# Connectors.net
KiCad netlist of a schematic drawn in Altium Designer
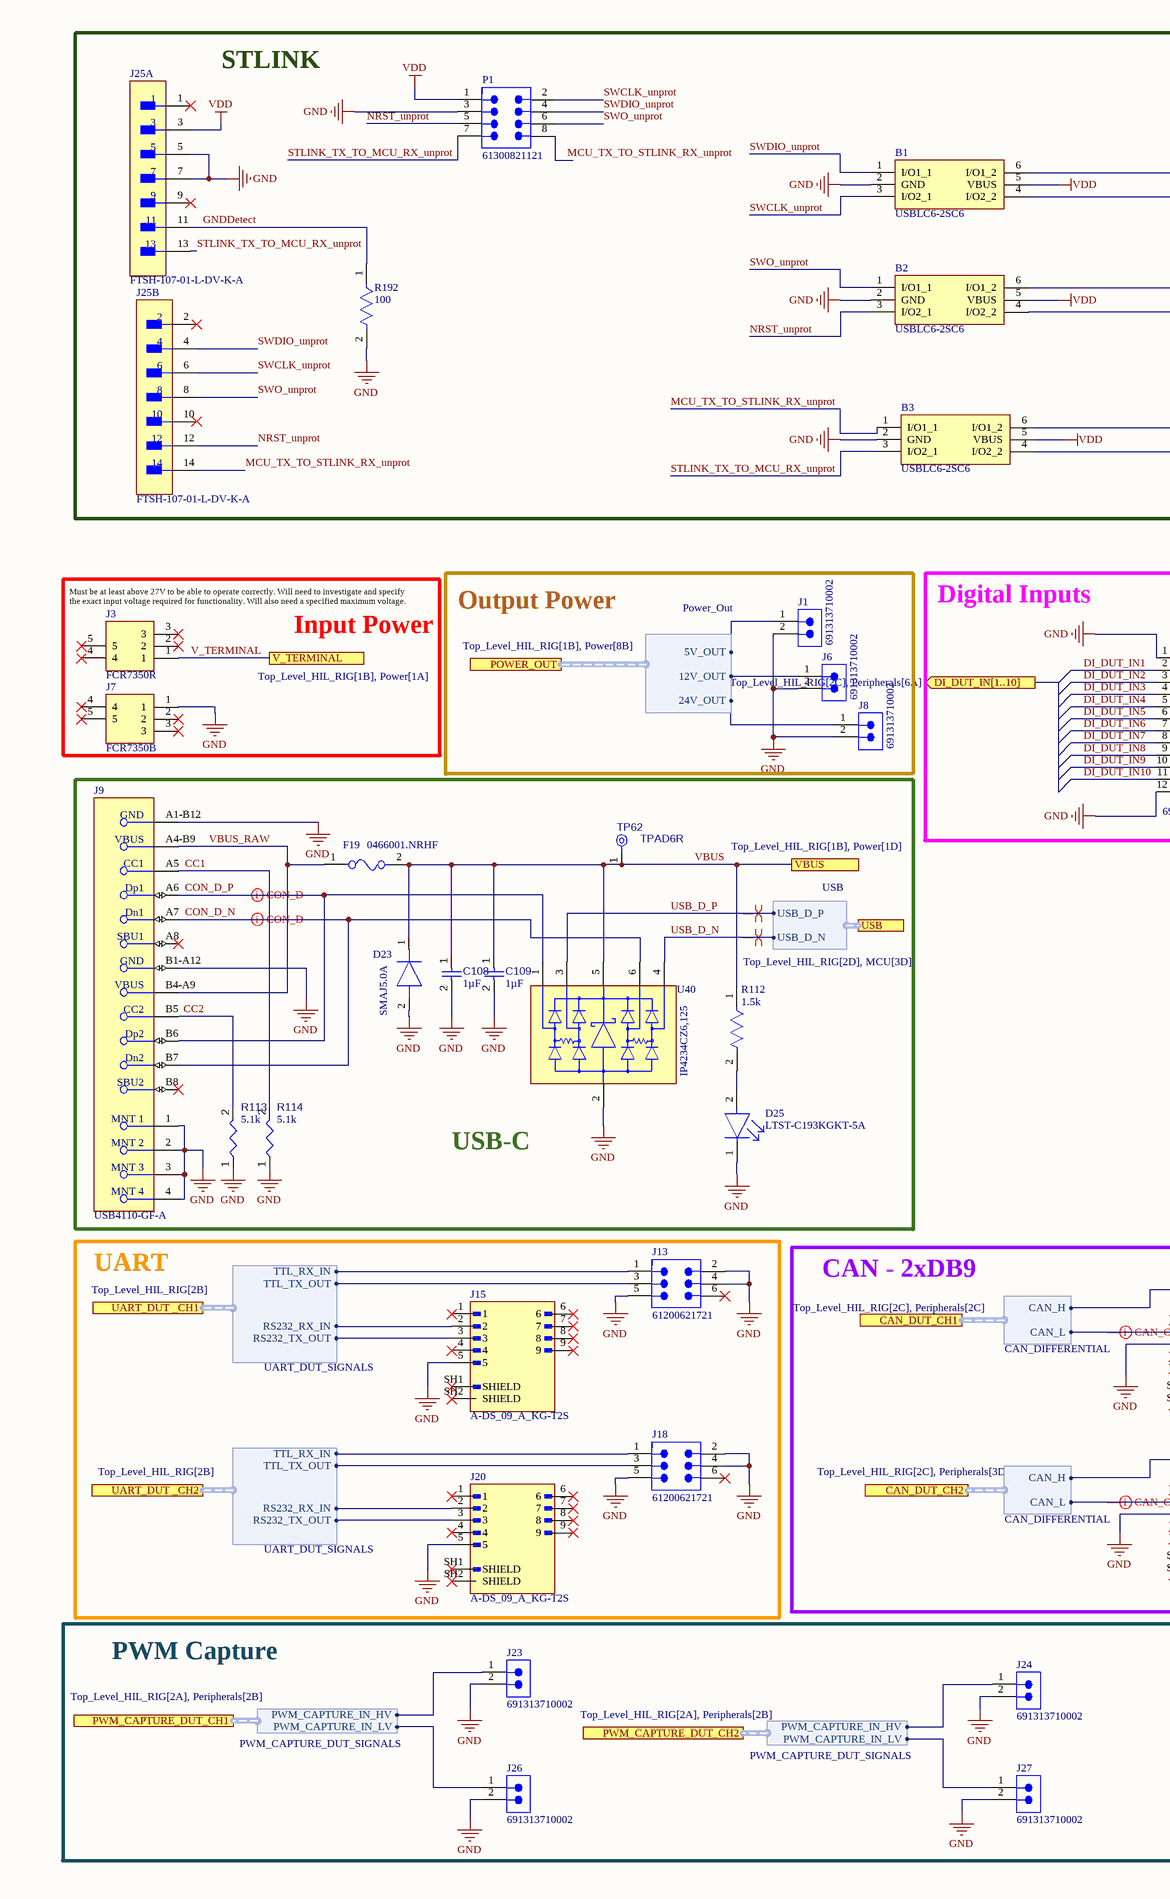
[diagram p0:  Connectors.SchDoc, left]
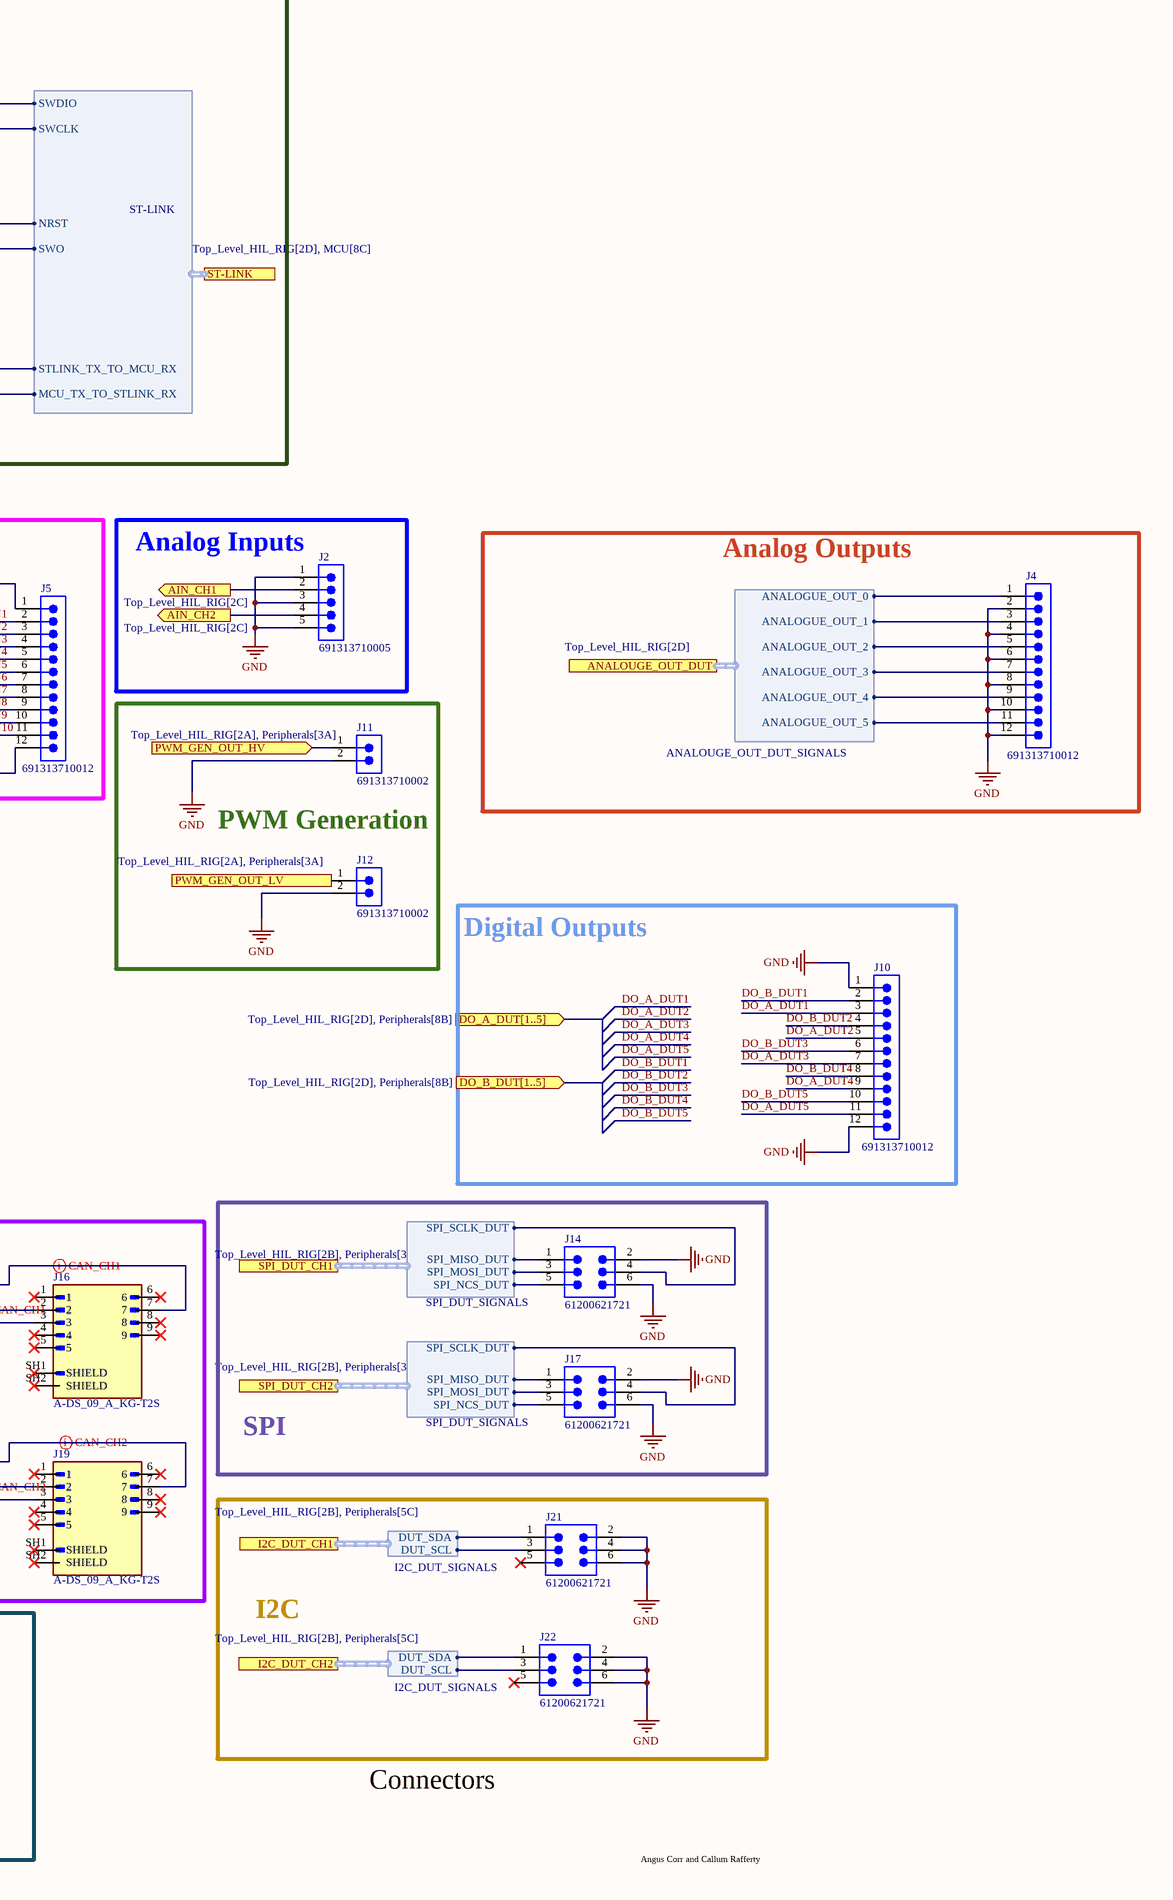
[diagram p1:  Connectors.SchDoc, right]

(export (version "E")
  (design (tool "Eeschema 10.0.6"))
  (components
    (comp (ref "B1")
      (value "USBLC6-2SC6")
      (footprint "SOT95P280X145-6N")
      (description "TVS Diode Array Uni-Directional USBLC6-2SC6 17V, SOT-23 6-Pin")
      (fields (field (name "MOUSER PART NUMBER") "511-USBLC6-2SC6"))
      (libsource (lib "HIL RIG FYP") (part "USBLC6-2SC6"))
    )
    (comp (ref "B2")
      (value "USBLC6-2SC6")
      (footprint "SOT95P280X145-6N")
      (description "TVS Diode Array Uni-Directional USBLC6-2SC6 17V, SOT-23 6-Pin")
      (fields (field (name "MOUSER PART NUMBER") "511-USBLC6-2SC6"))
      (libsource (lib "HIL RIG FYP") (part "USBLC6-2SC6"))
    )
    (comp (ref "B3")
      (value "USBLC6-2SC6")
      (footprint "SOT95P280X145-6N")
      (description "TVS Diode Array Uni-Directional USBLC6-2SC6 17V, SOT-23 6-Pin")
      (fields (field (name "MOUSER PART NUMBER") "511-USBLC6-2SC6"))
      (libsource (lib "HIL RIG FYP") (part "USBLC6-2SC6"))
    )
    (comp (ref "C108")
      (value "1µF")
      (footprint "CAPC1608X90X40LL10T20")
      (description "Chip Capacitor, 1 uF, +/- 10%, 25 V, 0603 (1608 Metric)")
      (fields (field (name "TOLERANCE") "10%") (field (name "Comment") "Capacitor 1 uF +/- 10% 25 V 0603"))
      (libsource (lib "HIL RIG FYP") (part "CAP-NP-2"))
    )
    (comp (ref "C109")
      (value "1µF")
      (footprint "CAPC1608X90X40LL10T20")
      (description "Chip Capacitor, 1 uF, +/- 10%, 25 V, 0603 (1608 Metric)")
      (fields (field (name "TOLERANCE") "10%") (field (name "Comment") "Capacitor 1 uF +/- 10% 25 V 0603"))
      (libsource (lib "HIL RIG FYP") (part "CAP-NP-2"))
    )
    (comp (ref "D23")
      (value "SMAJ5.0A")
      (footprint "DIOM5026X229N")
      (description "BOURNS - SMAJ5.0A - TVS Diode")
      (fields (field (name "MOUSER PART NUMBER") "652-SMAJ5.0A"))
      (libsource (lib "HIL RIG FYP") (part "SMAJ5.0A"))
    )
    (comp (ref "D25")
      (value "LTST-C193KGKT-5A")
      (footprint "FP-LTST-C193KGKT-5A-MFG")
      (description "LED yellow green 0603 wavelength 567.5~576.5nm light intensity 4.5~28mcd Front Mounting")
      (libsource (lib "HIL RIG FYP") (part "8706943c75ba83719d021d2fdc84c58"))
    )
    (comp (ref "F19")
      (value "0466001.NRHF")
      (footprint "FP-0466-MFG")
      (description "Electric Fuse, Fast Blow, 1A, 63VAC, 63VDC, 50A (IR), Supplemental, Surface Mount, 1206")
      (libsource (lib "HIL RIG FYP") (part "5bcf9b9f640e542cf0359d10258e979"))
    )
    (comp (ref "J1")
      (value "691313710002")
      (footprint "691313710002")
      (description "WR-TBL Terminal block - PCB Header - THT")
      (fields (field (name "VOLTAGE") "300V"))
      (libsource (lib "HIL RIG FYP") (part "TBL - 1R - 02P - Male"))
    )
    (comp (ref "J2")
      (value "691313710005")
      (footprint "691313710005")
      (description "Terminal Block, 5.00MM Pitch, Close Horizontal Pcb Header, 300VAC, 5 Pins")
      (fields (field (name "VOLTAGE") "300V"))
      (libsource (lib "HIL RIG FYP") (part "TBL - 1R - 05P - Male"))
    )
    (comp (ref "J3")
      (value "FCR7350R")
      (footprint "FCR7350R")
      (description "CLIFF ELECTRONIC COMPONENTS - FCR7350R - SOCKET")
      (libsource (lib "") (part "FCR7350R_1"))
    )
    (comp (ref "J4")
      (value "691313710012")
      (footprint "691313710012")
      (description "Terminal Block, R/A Header, 12Pos, Th Rohs Compliant: Yes")
      (libsource (lib "HIL RIG FYP") (part "TBL - 1R - 12P - Male"))
    )
    (comp (ref "J5")
      (value "691313710012")
      (footprint "691313710012")
      (description "Terminal Block, R/A Header, 12Pos, Th Rohs Compliant: Yes")
      (libsource (lib "HIL RIG FYP") (part "TBL - 1R - 12P - Male"))
    )
    (comp (ref "J6")
      (value "691313710002")
      (footprint "691313710002")
      (description "WR-TBL Terminal block - PCB Header - THT")
      (fields (field (name "VOLTAGE") "300V"))
      (libsource (lib "HIL RIG FYP") (part "TBL - 1R - 02P - Male"))
    )
    (comp (ref "J7")
      (value "FCR7350B")
      (footprint "FCR7350B")
      (description "Banana Jack Connector Standard Banana Solder Black Female  Through Hole")
      (libsource (lib "HIL RIG FYP") (part "FCR7350R"))
    )
    (comp (ref "J8")
      (value "691313710002")
      (footprint "691313710002")
      (description "WR-TBL Terminal block - PCB Header - THT")
      (fields (field (name "VOLTAGE") "300V"))
      (libsource (lib "HIL RIG FYP") (part "TBL - 1R - 02P - Male"))
    )
    (comp (ref "J9")
      (value "USB4110-GF-A")
      (footprint "FP-USB4110-GF-A-MFG")
      (description "USB Connector, 16 Contact(s), Male, Right Angle, Surface Mount Terminal, Locking, Receptacle")
      (libsource (lib "HIL RIG FYP") (part "e23f2b38bb3c3f98e683ebab9ede730"))
    )
    (comp (ref "J10")
      (value "691313710012")
      (footprint "691313710012")
      (description "Terminal Block, R/A Header, 12Pos, Th Rohs Compliant: Yes")
      (libsource (lib "HIL RIG FYP") (part "TBL - 1R - 12P - Male"))
    )
    (comp (ref "J11")
      (value "691313710002")
      (footprint "691313710002")
      (description "WR-TBL Terminal block - PCB Header - THT")
      (fields (field (name "VOLTAGE") "300V"))
      (libsource (lib "HIL RIG FYP") (part "TBL - 1R - 02P - Male"))
    )
    (comp (ref "J12")
      (value "691313710002")
      (footprint "691313710002")
      (description "WR-TBL Terminal block - PCB Header - THT")
      (fields (field (name "VOLTAGE") "300V"))
      (libsource (lib "HIL RIG FYP") (part "TBL - 1R - 02P - Male"))
    )
    (comp (ref "J13")
      (value "61200621721")
      (footprint "61200621721")
      (description "Wr-bhd; 2.54MM Pitch 6 Way 2 Row Shrouded Right Angle Pcb Header, Surface Mount")
      (libsource (lib "HIL RIG FYP") (part "Header_Male_2R_06P"))
    )
    (comp (ref "J14")
      (value "61200621721")
      (footprint "61200621721")
      (description "Wr-bhd; 2.54MM Pitch 6 Way 2 Row Shrouded Right Angle Pcb Header, Surface Mount")
      (libsource (lib "HIL RIG FYP") (part "Header_Male_2R_06P"))
    )
    (comp (ref "J15")
      (value "A-DS_09_A_KG-T2S")
      (footprint "ASSMANN_A-DS_09_A_KG-T2S")
      (description "9 Position D-Sub Plug, Male Pins Connector")
      (fields (field (name "MF") "Assmann WSW") (field (name "MP") "A-DS 09 A/KG-T2S"))
      (libsource (lib "HIL RIG FYP") (part "A-DS_09_A_KG-T2S"))
    )
    (comp (ref "J16")
      (value "A-DS_09_A_KG-T2S")
      (footprint "ASSMANN_A-DS_09_A_KG-T2S")
      (description "9 Position D-Sub Plug, Male Pins Connector")
      (fields (field (name "MF") "Assmann WSW") (field (name "MP") "A-DS 09 A/KG-T2S"))
      (libsource (lib "HIL RIG FYP") (part "A-DS_09_A_KG-T2S"))
    )
    (comp (ref "J17")
      (value "61200621721")
      (footprint "61200621721")
      (description "Wr-bhd; 2.54MM Pitch 6 Way 2 Row Shrouded Right Angle Pcb Header, Surface Mount")
      (libsource (lib "HIL RIG FYP") (part "Header_Male_2R_06P"))
    )
    (comp (ref "J18")
      (value "61200621721")
      (footprint "61200621721")
      (description "Wr-bhd; 2.54MM Pitch 6 Way 2 Row Shrouded Right Angle Pcb Header, Surface Mount")
      (libsource (lib "HIL RIG FYP") (part "Header_Male_2R_06P"))
    )
    (comp (ref "J19")
      (value "A-DS_09_A_KG-T2S")
      (footprint "ASSMANN_A-DS_09_A_KG-T2S")
      (description "9 Position D-Sub Plug, Male Pins Connector")
      (fields (field (name "MF") "Assmann WSW") (field (name "MP") "A-DS 09 A/KG-T2S"))
      (libsource (lib "HIL RIG FYP") (part "A-DS_09_A_KG-T2S"))
    )
    (comp (ref "J20")
      (value "A-DS_09_A_KG-T2S")
      (footprint "ASSMANN_A-DS_09_A_KG-T2S")
      (description "9 Position D-Sub Plug, Male Pins Connector")
      (fields (field (name "MF") "Assmann WSW") (field (name "MP") "A-DS 09 A/KG-T2S"))
      (libsource (lib "HIL RIG FYP") (part "A-DS_09_A_KG-T2S"))
    )
    (comp (ref "J21")
      (value "61200621721")
      (footprint "61200621721")
      (description "Wr-bhd; 2.54MM Pitch 6 Way 2 Row Shrouded Right Angle Pcb Header, Surface Mount")
      (libsource (lib "HIL RIG FYP") (part "Header_Male_2R_06P"))
    )
    (comp (ref "J22")
      (value "61200621721")
      (footprint "61200621721")
      (description "Wr-bhd; 2.54MM Pitch 6 Way 2 Row Shrouded Right Angle Pcb Header, Surface Mount")
      (libsource (lib "HIL RIG FYP") (part "Header_Male_2R_06P"))
    )
    (comp (ref "J23")
      (value "691313710002")
      (footprint "691313710002")
      (description "WR-TBL Terminal block - PCB Header - THT")
      (fields (field (name "VOLTAGE") "300V"))
      (libsource (lib "HIL RIG FYP") (part "TBL - 1R - 02P - Male"))
    )
    (comp (ref "J24")
      (value "691313710002")
      (footprint "691313710002")
      (description "WR-TBL Terminal block - PCB Header - THT")
      (fields (field (name "VOLTAGE") "300V"))
      (libsource (lib "HIL RIG FYP") (part "TBL - 1R - 02P - Male"))
    )
    (comp (ref "J25")
      (value "FTSH-107-01-L-DV-K-A")
      (footprint "FP-FTSH-107-01-L-DV-K-A-MFG")
      (description "Conn Unshrouded Header HDR 14 POS 1.27mm Solder ST Top Entry SMD TIGER CLAW™ Tube")
      (libsource (lib "HIL RIG FYP") (part "45cc164b9edde9e1ad516d884ad4e1e"))
    )
    (comp (ref "J26")
      (value "691313710002")
      (footprint "691313710002")
      (description "WR-TBL Terminal block - PCB Header - THT")
      (fields (field (name "VOLTAGE") "300V"))
      (libsource (lib "HIL RIG FYP") (part "TBL - 1R - 02P - Male"))
    )
    (comp (ref "J27")
      (value "691313710002")
      (footprint "691313710002")
      (description "WR-TBL Terminal block - PCB Header - THT")
      (fields (field (name "VOLTAGE") "300V"))
      (libsource (lib "HIL RIG FYP") (part "TBL - 1R - 02P - Male"))
    )
    (comp (ref "P1")
      (value "61300821121")
      (footprint "61300821121")
      (description "Conn Unshrouded Header HDR 8 POS 2.54mm Solder ST Top Entry Thru-Hole Bag")
      (libsource (lib "HIL RIG FYP") (part "Header_Male_2R_08P"))
    )
    (comp (ref "R112")
      (value "1.5k")
      (footprint "FP-RT0603-IPC_C")
      (description "Res Thin Film 0603 1.5K Ohm 0.1% 1/10W ±25ppm/°C Molded SMD SMD Paper T/R")
      (fields (field (name "TOLERANCE") "0.1%") (field (name "Comment") "RT0603BRD071K5L"))
      (libsource (lib "HIL RIG FYP") (part "1029c3af85768c4190bb7ad29bc67b5"))
    )
    (comp (ref "R113")
      (value "5.1k")
      (footprint "FP-AC0603-IPC_C")
      (description "Res Thick Film 0603 5.1K Ohm 1% 0.1W(1/10W) ±100ppm/C Pad SMD Automotive T/R")
      (fields (field (name "TOLERANCE") "1%") (field (name "Comment") "AC0603FR-075K1L"))
      (libsource (lib "HIL RIG FYP") (part "RES-2"))
    )
    (comp (ref "R114")
      (value "5.1k")
      (footprint "FP-AC0603-IPC_C")
      (description "Res Thick Film 0603 5.1K Ohm 1% 0.1W(1/10W) ±100ppm/C Pad SMD Automotive T/R")
      (fields (field (name "TOLERANCE") "1%") (field (name "Comment") "AC0603FR-075K1L"))
      (libsource (lib "HIL RIG FYP") (part "RES-2"))
    )
    (comp (ref "R192")
      (value "100")
      (footprint "FP-RT0603-IPC_C")
      (description "100mW Thin Film Resistor 75V ±25ppm/℃ ±0.1% 100Ω 0603 Chip Resistor - Surface Mount ROHS")
      (fields (field (name "TOLERANCE") "0.1%") (field (name "Comment") "RT0603BRD07100RL"))
      (libsource (lib "HIL RIG FYP") (part "1029c3af85768c4190bb7ad29bc67b5"))
    )
    (comp (ref "TP62")
      (value "TPAD6R")
      (footprint "TP06R")
      (description "0.6mm round")
      (libsource (lib "HIL RIG FYP") (part "CMP-001-0001-4"))
    )
    (comp (ref "U40")
      (value "IP4234CZ6,125")
      (footprint "Nexperia_SOT457_IPC_C")
      (description "IP4234CZ6 Series 4 Channel Single USB 2.0 ESD Protection Surface Mount - TSOP-6")
      (libsource (lib "HIL RIG FYP") (part "IP4234CZ6_125"))
    )
  )
  (nets
    (net (code "10") (name "/5V_OUT") (class "Default")
      (node (ref "J1") (pin "1") (pinfunction "1_1") (pintype "passive"))
    )
    (net (code "11") (name "/12V_OUT") (class "Default")
      (node (ref "J6") (pin "1") (pinfunction "1_1") (pintype "passive"))
    )
    (net (code "12") (name "/24V_OUT") (class "Default")
      (node (ref "J8") (pin "1") (pinfunction "1_1") (pintype "passive"))
    )
    (net (code "13") (name "/AIN_CH1") (class "Default")
      (node (ref "J2") (pin "2") (pinfunction "2_2") (pintype "passive"))
    )
    (net (code "14") (name "/AIN_CH2") (class "Default")
      (node (ref "J2") (pin "4") (pinfunction "4_4") (pintype "passive"))
    )
    (net (code "15") (name "/ANALOGUE_OUT_0") (class "Default")
      (node (ref "J4") (pin "1") (pinfunction "1_1") (pintype "passive"))
    )
    (net (code "16") (name "/ANALOGUE_OUT_1") (class "Default")
      (node (ref "J4") (pin "3") (pinfunction "3_3") (pintype "passive"))
    )
    (net (code "17") (name "/ANALOGUE_OUT_2") (class "Default")
      (node (ref "J4") (pin "5") (pinfunction "5_5") (pintype "passive"))
    )
    (net (code "18") (name "/ANALOGUE_OUT_3") (class "Default")
      (node (ref "J4") (pin "7") (pinfunction "7_7") (pintype "passive"))
    )
    (net (code "19") (name "/ANALOGUE_OUT_4") (class "Default")
      (node (ref "J4") (pin "9") (pinfunction "9_9") (pintype "passive"))
    )
    (net (code "20") (name "/ANALOGUE_OUT_5") (class "Default")
      (node (ref "J4") (pin "11") (pinfunction "11_11") (pintype "passive"))
    )
    (net (code "21") (name "/CC1") (class "Default")
      (node (ref "J9") (pin "A5") (pinfunction "CC1_A5") (pintype "power_in"))
      (node (ref "R114") (pin "2") (pinfunction "2_2") (pintype "passive"))
    )
    (net (code "22") (name "/CC2") (class "Default")
      (node (ref "J9") (pin "B5") (pinfunction "CC2_B5") (pintype "power_in"))
      (node (ref "R113") (pin "2") (pinfunction "2_2") (pintype "passive"))
    )
    (net (code "23") (name "/CON_D_N") (class "Default")
      (node (ref "J9") (pin "A7") (pinfunction "Dn1_A7") (pintype "bidirectional"))
      (node (ref "J9") (pin "B7") (pinfunction "Dn2_B7") (pintype "bidirectional"))
      (node (ref "U40") (pin "6") (pinfunction "6_6") (pintype "passive"))
    )
    (net (code "24") (name "/CON_D_P") (class "Default")
      (node (ref "J9") (pin "A6") (pinfunction "Dp1_A6") (pintype "bidirectional"))
      (node (ref "J9") (pin "B6") (pinfunction "Dp2_B6") (pintype "bidirectional"))
      (node (ref "U40") (pin "1") (pinfunction "1_1") (pintype "passive"))
    )
    (net (code "25") (name "/DI_DUT_IN1") (class "Default")
      (node (ref "J5") (pin "2") (pinfunction "2_2") (pintype "passive"))
    )
    (net (code "26") (name "/DI_DUT_IN2") (class "Default")
      (node (ref "J5") (pin "3") (pinfunction "3_3") (pintype "passive"))
    )
    (net (code "27") (name "/DI_DUT_IN3") (class "Default")
      (node (ref "J5") (pin "4") (pinfunction "4_4") (pintype "passive"))
    )
    (net (code "28") (name "/DI_DUT_IN4") (class "Default")
      (node (ref "J5") (pin "5") (pinfunction "5_5") (pintype "passive"))
    )
    (net (code "29") (name "/DI_DUT_IN5") (class "Default")
      (node (ref "J5") (pin "6") (pinfunction "6_6") (pintype "passive"))
    )
    (net (code "30") (name "/DI_DUT_IN6") (class "Default")
      (node (ref "J5") (pin "7") (pinfunction "7_7") (pintype "passive"))
    )
    (net (code "31") (name "/DI_DUT_IN7") (class "Default")
      (node (ref "J5") (pin "8") (pinfunction "8_8") (pintype "passive"))
    )
    (net (code "32") (name "/DI_DUT_IN8") (class "Default")
      (node (ref "J5") (pin "9") (pinfunction "9_9") (pintype "passive"))
    )
    (net (code "33") (name "/DI_DUT_IN9") (class "Default")
      (node (ref "J5") (pin "10") (pinfunction "10_10") (pintype "passive"))
    )
    (net (code "34") (name "/DI_DUT_IN10") (class "Default")
      (node (ref "J5") (pin "11") (pinfunction "11_11") (pintype "passive"))
    )
    (net (code "36") (name "/DO_A_DUT1") (class "Default")
      (node (ref "J10") (pin "3") (pinfunction "3_3") (pintype "passive"))
    )
    (net (code "37") (name "/DO_A_DUT2") (class "Default")
      (node (ref "J10") (pin "5") (pinfunction "5_5") (pintype "passive"))
    )
    (net (code "38") (name "/DO_A_DUT3") (class "Default")
      (node (ref "J10") (pin "7") (pinfunction "7_7") (pintype "passive"))
    )
    (net (code "39") (name "/DO_A_DUT4") (class "Default")
      (node (ref "J10") (pin "9") (pinfunction "9_9") (pintype "passive"))
    )
    (net (code "40") (name "/DO_A_DUT5") (class "Default")
      (node (ref "J10") (pin "11") (pinfunction "11_11") (pintype "passive"))
    )
    (net (code "42") (name "/DO_B_DUT1") (class "Default")
      (node (ref "J10") (pin "2") (pinfunction "2_2") (pintype "passive"))
    )
    (net (code "43") (name "/DO_B_DUT2") (class "Default")
      (node (ref "J10") (pin "4") (pinfunction "4_4") (pintype "passive"))
    )
    (net (code "44") (name "/DO_B_DUT3") (class "Default")
      (node (ref "J10") (pin "6") (pinfunction "6_6") (pintype "passive"))
    )
    (net (code "45") (name "/DO_B_DUT4") (class "Default")
      (node (ref "J10") (pin "8") (pinfunction "8_8") (pintype "passive"))
    )
    (net (code "46") (name "/DO_B_DUT5") (class "Default")
      (node (ref "J10") (pin "10") (pinfunction "10_10") (pintype "passive"))
    )
    (net (code "48") (name "/GNDDetect") (class "Default")
      (node (ref "J25") (pin "11") (pinfunction "11_11") (pintype "passive"))
      (node (ref "R192") (pin "1") (pinfunction "1_1") (pintype "passive"))
    )
    (net (code "49") (name "/MCU_TX_TO_STLINK_RX") (class "Default")
      (node (ref "B3") (pin "4") (pinfunction "I/O2_2_4") (pintype "passive"))
    )
    (net (code "50") (name "/MCU_TX_TO_STLINK_RX_unprot") (class "Default")
      (node (ref "B3") (pin "1") (pinfunction "I/O1_1_1") (pintype "passive"))
      (node (ref "J25") (pin "14") (pinfunction "14_14") (pintype "passive"))
      (node (ref "P1") (pin "8") (pinfunction "8_8") (pintype "passive"))
    )
    (net (code "51") (name "/NRST") (class "Default")
      (node (ref "B2") (pin "6") (pinfunction "I/O1_2_6") (pintype "passive"))
    )
    (net (code "52") (name "/NRST_unprot") (class "Default")
      (node (ref "B2") (pin "3") (pinfunction "I/O2_1_3") (pintype "passive"))
      (node (ref "J25") (pin "12") (pinfunction "12_12") (pintype "passive"))
      (node (ref "P1") (pin "5") (pinfunction "5_5") (pintype "passive"))
    )
    (net (code "53") (name "/PWM_GEN_OUT_HV") (class "Default")
      (node (ref "J11") (pin "1") (pinfunction "1_1") (pintype "passive"))
    )
    (net (code "54") (name "/PWM_GEN_OUT_LV") (class "Default")
      (node (ref "J12") (pin "1") (pinfunction "1_1") (pintype "passive"))
    )
    (net (code "55") (name "/STLINK_TX_TO_MCU_RX") (class "Default")
      (node (ref "B3") (pin "6") (pinfunction "I/O1_2_6") (pintype "passive"))
    )
    (net (code "56") (name "/STLINK_TX_TO_MCU_RX_unprot") (class "Default")
      (node (ref "B3") (pin "3") (pinfunction "I/O2_1_3") (pintype "passive"))
      (node (ref "J25") (pin "13") (pinfunction "13_13") (pintype "passive"))
      (node (ref "P1") (pin "7") (pinfunction "7_7") (pintype "passive"))
    )
    (net (code "57") (name "/SWCLK") (class "Default")
      (node (ref "B1") (pin "4") (pinfunction "I/O2_2_4") (pintype "passive"))
    )
    (net (code "58") (name "/SWCLK_unprot") (class "Default")
      (node (ref "B1") (pin "3") (pinfunction "I/O2_1_3") (pintype "passive"))
      (node (ref "J25") (pin "6") (pinfunction "6_6") (pintype "passive"))
      (node (ref "P1") (pin "2") (pinfunction "2_2") (pintype "passive"))
    )
    (net (code "59") (name "/SWDIO") (class "Default")
      (node (ref "B1") (pin "6") (pinfunction "I/O1_2_6") (pintype "passive"))
    )
    (net (code "60") (name "/SWDIO_unprot") (class "Default")
      (node (ref "B1") (pin "1") (pinfunction "I/O1_1_1") (pintype "passive"))
      (node (ref "J25") (pin "4") (pinfunction "4_4") (pintype "passive"))
      (node (ref "P1") (pin "4") (pinfunction "4_4") (pintype "passive"))
    )
    (net (code "61") (name "/SWO") (class "Default")
      (node (ref "B2") (pin "4") (pinfunction "I/O2_2_4") (pintype "passive"))
    )
    (net (code "62") (name "/SWO_unprot") (class "Default")
      (node (ref "B2") (pin "1") (pinfunction "I/O1_1_1") (pintype "passive"))
      (node (ref "J25") (pin "8") (pinfunction "8_8") (pintype "passive"))
      (node (ref "P1") (pin "6") (pinfunction "6_6") (pintype "passive"))
    )
    (net (code "63") (name "/USB_D_N") (class "Default")
      (node (ref "U40") (pin "4") (pinfunction "4_4") (pintype "passive"))
    )
    (net (code "64") (name "/USB_D_P") (class "Default")
      (node (ref "U40") (pin "3") (pinfunction "3_3") (pintype "passive"))
    )
    (net (code "65") (name "/VBUS") (class "Default")
      (node (ref "C108") (pin "1") (pinfunction "1_1") (pintype "passive"))
      (node (ref "C109") (pin "1") (pinfunction "1_1") (pintype "passive"))
      (node (ref "D23") (pin "1") (pinfunction "K_1") (pintype "passive"))
      (node (ref "F19") (pin "2") (pinfunction "2_2") (pintype "passive"))
      (node (ref "R112") (pin "1") (pinfunction "1_1") (pintype "passive"))
      (node (ref "TP62") (pin "1") (pinfunction "TP_1") (pintype "passive"))
      (node (ref "U40") (pin "5") (pinfunction "5_5") (pintype "passive"))
    )
    (net (code "66") (name "/VBUS_RAW") (class "Default")
      (node (ref "F19") (pin "1") (pinfunction "1_1") (pintype "passive"))
      (node (ref "J9") (pin "A4-B9") (pinfunction "VBUS_A4-B9") (pintype "power_in"))
      (node (ref "J9") (pin "B4-A9") (pinfunction "VBUS_B4-A9") (pintype "power_in"))
    )
    (net (code "67") (name "/V_TERMINAL") (class "Default")
      (node (ref "J3") (pin "1") (pinfunction "1_1") (pintype "passive"))
    )
    (net (code "77") (name "GND") (class "Default")
      (node (ref "B1") (pin "2") (pinfunction "GND_2") (pintype "passive"))
      (node (ref "B2") (pin "2") (pinfunction "GND_2") (pintype "passive"))
      (node (ref "B3") (pin "2") (pinfunction "GND_2") (pintype "passive"))
      (node (ref "C108") (pin "2") (pinfunction "2_2") (pintype "passive"))
      (node (ref "C109") (pin "2") (pinfunction "2_2") (pintype "passive"))
      (node (ref "D23") (pin "2") (pinfunction "A_2") (pintype "passive"))
      (node (ref "D25") (pin "1") (pinfunction "C_1") (pintype "passive"))
      (node (ref "J1") (pin "2") (pinfunction "2_2") (pintype "passive"))
      (node (ref "J10") (pin "1") (pinfunction "1_1") (pintype "passive"))
      (node (ref "J10") (pin "12") (pinfunction "12_12") (pintype "passive"))
      (node (ref "J11") (pin "2") (pinfunction "2_2") (pintype "passive"))
      (node (ref "J12") (pin "2") (pinfunction "2_2") (pintype "passive"))
      (node (ref "J13") (pin "2") (pinfunction "2_2") (pintype "passive"))
      (node (ref "J13") (pin "4") (pinfunction "4_4") (pintype "passive"))
      (node (ref "J13") (pin "5") (pinfunction "5_5") (pintype "passive"))
      (node (ref "J14") (pin "2") (pinfunction "2_2") (pintype "passive"))
      (node (ref "J14") (pin "6") (pinfunction "6_6") (pintype "passive"))
      (node (ref "J15") (pin "5") (pinfunction "5_5") (pintype "passive"))
      (node (ref "J16") (pin "3") (pinfunction "3_3") (pintype "passive"))
      (node (ref "J17") (pin "2") (pinfunction "2_2") (pintype "passive"))
      (node (ref "J17") (pin "6") (pinfunction "6_6") (pintype "passive"))
      (node (ref "J18") (pin "2") (pinfunction "2_2") (pintype "passive"))
      (node (ref "J18") (pin "4") (pinfunction "4_4") (pintype "passive"))
      (node (ref "J18") (pin "5") (pinfunction "5_5") (pintype "passive"))
      (node (ref "J19") (pin "3") (pinfunction "3_3") (pintype "passive"))
      (node (ref "J2") (pin "1") (pinfunction "1_1") (pintype "passive"))
      (node (ref "J2") (pin "3") (pinfunction "3_3") (pintype "passive"))
      (node (ref "J2") (pin "5") (pinfunction "5_5") (pintype "passive"))
      (node (ref "J20") (pin "5") (pinfunction "5_5") (pintype "passive"))
      (node (ref "J21") (pin "2") (pinfunction "2_2") (pintype "passive"))
      (node (ref "J21") (pin "4") (pinfunction "4_4") (pintype "passive"))
      (node (ref "J21") (pin "6") (pinfunction "6_6") (pintype "passive"))
      (node (ref "J22") (pin "2") (pinfunction "2_2") (pintype "passive"))
      (node (ref "J22") (pin "4") (pinfunction "4_4") (pintype "passive"))
      (node (ref "J22") (pin "6") (pinfunction "6_6") (pintype "passive"))
      (node (ref "J23") (pin "2") (pinfunction "2_2") (pintype "passive"))
      (node (ref "J24") (pin "2") (pinfunction "2_2") (pintype "passive"))
      (node (ref "J25") (pin "5") (pinfunction "5_5") (pintype "passive"))
      (node (ref "J25") (pin "7") (pinfunction "7_7") (pintype "passive"))
      (node (ref "J26") (pin "2") (pinfunction "2_2") (pintype "passive"))
      (node (ref "J27") (pin "2") (pinfunction "2_2") (pintype "passive"))
      (node (ref "J4") (pin "10") (pinfunction "10_10") (pintype "passive"))
      (node (ref "J4") (pin "12") (pinfunction "12_12") (pintype "passive"))
      (node (ref "J4") (pin "2") (pinfunction "2_2") (pintype "passive"))
      (node (ref "J4") (pin "4") (pinfunction "4_4") (pintype "passive"))
      (node (ref "J4") (pin "6") (pinfunction "6_6") (pintype "passive"))
      (node (ref "J4") (pin "8") (pinfunction "8_8") (pintype "passive"))
      (node (ref "J5") (pin "1") (pinfunction "1_1") (pintype "passive"))
      (node (ref "J5") (pin "12") (pinfunction "12_12") (pintype "passive"))
      (node (ref "J6") (pin "2") (pinfunction "2_2") (pintype "passive"))
      (node (ref "J7") (pin "1") (pinfunction "1_1") (pintype "passive"))
      (node (ref "J8") (pin "2") (pinfunction "2_2") (pintype "passive"))
      (node (ref "J9") (pin "1") (pinfunction "MNT_1_1") (pintype "passive"))
      (node (ref "J9") (pin "2") (pinfunction "MNT_2_2") (pintype "passive"))
      (node (ref "J9") (pin "3") (pinfunction "MNT_3_3") (pintype "passive"))
      (node (ref "J9") (pin "4") (pinfunction "MNT_4_4") (pintype "passive"))
      (node (ref "J9") (pin "A1-B12") (pinfunction "GND_A1-B12") (pintype "passive"))
      (node (ref "J9") (pin "B1-A12") (pinfunction "GND_B1-A12") (pintype "bidirectional"))
      (node (ref "P1") (pin "3") (pinfunction "3_3") (pintype "passive"))
      (node (ref "R113") (pin "1") (pinfunction "1_1") (pintype "passive"))
      (node (ref "R114") (pin "1") (pinfunction "1_1") (pintype "passive"))
      (node (ref "R192") (pin "2") (pinfunction "2_2") (pintype "passive"))
      (node (ref "U40") (pin "2") (pinfunction "2_2") (pintype "passive"))
    )
    (net (code "78") (name "Net-(D25-A)") (class "Default")
      (node (ref "D25") (pin "2") (pinfunction "A_2") (pintype "passive"))
      (node (ref "R112") (pin "2") (pinfunction "2_2") (pintype "passive"))
    )
    (net (code "79") (name "VDD") (class "Default")
      (node (ref "B1") (pin "5") (pinfunction "VBUS_5") (pintype "passive"))
      (node (ref "B2") (pin "5") (pinfunction "VBUS_5") (pintype "passive"))
      (node (ref "B3") (pin "5") (pinfunction "VBUS_5") (pintype "passive"))
      (node (ref "J25") (pin "3") (pinfunction "3_3") (pintype "passive"))
      (node (ref "P1") (pin "1") (pinfunction "1_1") (pintype "passive"))
    )
    (net (code "80") (name "unconnected-(J3-Pad2)") (class "Default")
      (node (ref "J3") (pin "2") (pinfunction "2_2") (pintype "passive+no_connect"))
    )
    (net (code "81") (name "unconnected-(J3-Pad3)") (class "Default")
      (node (ref "J3") (pin "3") (pinfunction "3_3") (pintype "passive+no_connect"))
    )
    (net (code "82") (name "unconnected-(J3-Pad4)") (class "Default")
      (node (ref "J3") (pin "4") (pinfunction "4_4") (pintype "passive+no_connect"))
    )
    (net (code "83") (name "unconnected-(J3-Pad5)") (class "Default")
      (node (ref "J3") (pin "5") (pinfunction "5_5") (pintype "passive+no_connect"))
    )
    (net (code "84") (name "unconnected-(J7-Pad2)") (class "Default")
      (node (ref "J7") (pin "2") (pinfunction "2_2") (pintype "passive+no_connect"))
    )
    (net (code "85") (name "unconnected-(J7-Pad3)") (class "Default")
      (node (ref "J7") (pin "3") (pinfunction "3_3") (pintype "passive+no_connect"))
    )
    (net (code "86") (name "unconnected-(J7-Pad4)") (class "Default")
      (node (ref "J7") (pin "4") (pinfunction "4_4") (pintype "passive+no_connect"))
    )
    (net (code "87") (name "unconnected-(J7-Pad5)") (class "Default")
      (node (ref "J7") (pin "5") (pinfunction "5_5") (pintype "passive+no_connect"))
    )
    (net (code "88") (name "unconnected-(J9-SBU1-PadA8)") (class "Default")
      (node (ref "J9") (pin "A8") (pinfunction "SBU1_A8") (pintype "bidirectional+no_connect"))
    )
    (net (code "89") (name "unconnected-(J9-SBU2-PadB8)") (class "Default")
      (node (ref "J9") (pin "B8") (pinfunction "SBU2_B8") (pintype "bidirectional+no_connect"))
    )
    (net (code "90") (name "unconnected-(J13-Pad1)") (class "Default")
      (node (ref "J13") (pin "1") (pinfunction "1_1") (pintype "passive"))
    )
    (net (code "91") (name "unconnected-(J13-Pad3)") (class "Default")
      (node (ref "J13") (pin "3") (pinfunction "3_3") (pintype "passive"))
    )
    (net (code "92") (name "unconnected-(J13-Pad6)") (class "Default")
      (node (ref "J13") (pin "6") (pinfunction "6_6") (pintype "passive+no_connect"))
    )
    (net (code "93") (name "unconnected-(J14-Pad1)") (class "Default")
      (node (ref "J14") (pin "1") (pinfunction "1_1") (pintype "passive"))
    )
    (net (code "94") (name "unconnected-(J14-Pad3)") (class "Default")
      (node (ref "J14") (pin "3") (pinfunction "3_3") (pintype "passive"))
    )
    (net (code "95") (name "unconnected-(J14-Pad4)") (class "Default")
      (node (ref "J14") (pin "4") (pinfunction "4_4") (pintype "passive"))
    )
    (net (code "96") (name "unconnected-(J14-Pad5)") (class "Default")
      (node (ref "J14") (pin "5") (pinfunction "5_5") (pintype "passive"))
    )
    (net (code "97") (name "unconnected-(J15-Pad1)") (class "Default")
      (node (ref "J15") (pin "1") (pinfunction "1_1") (pintype "passive+no_connect"))
    )
    (net (code "98") (name "unconnected-(J15-Pad2)") (class "Default")
      (node (ref "J15") (pin "2") (pinfunction "2_2") (pintype "passive"))
    )
    (net (code "99") (name "unconnected-(J15-Pad3)") (class "Default")
      (node (ref "J15") (pin "3") (pinfunction "3_3") (pintype "passive"))
    )
    (net (code "100") (name "unconnected-(J15-Pad4)") (class "Default")
      (node (ref "J15") (pin "4") (pinfunction "4_4") (pintype "passive+no_connect"))
    )
    (net (code "101") (name "unconnected-(J15-Pad6)") (class "Default")
      (node (ref "J15") (pin "6") (pinfunction "6_6") (pintype "passive+no_connect"))
    )
    (net (code "102") (name "unconnected-(J15-Pad7)") (class "Default")
      (node (ref "J15") (pin "7") (pinfunction "7_7") (pintype "passive+no_connect"))
    )
    (net (code "103") (name "unconnected-(J15-Pad8)") (class "Default")
      (node (ref "J15") (pin "8") (pinfunction "8_8") (pintype "passive+no_connect"))
    )
    (net (code "104") (name "unconnected-(J15-Pad9)") (class "Default")
      (node (ref "J15") (pin "9") (pinfunction "9_9") (pintype "passive+no_connect"))
    )
    (net (code "105") (name "unconnected-(J15-SHIELD-PadSH1)") (class "Default")
      (node (ref "J15") (pin "SH1") (pinfunction "SHIELD_SH1") (pintype "passive+no_connect"))
    )
    (net (code "106") (name "unconnected-(J15-SHIELD-PadSH2)") (class "Default")
      (node (ref "J15") (pin "SH2") (pinfunction "SHIELD_SH2") (pintype "passive+no_connect"))
    )
    (net (code "107") (name "unconnected-(J16-Pad1)") (class "Default")
      (node (ref "J16") (pin "1") (pinfunction "1_1") (pintype "passive+no_connect"))
    )
    (net (code "108") (name "unconnected-(J16-Pad2)") (class "Default")
      (node (ref "J16") (pin "2") (pinfunction "2_2") (pintype "passive"))
    )
    (net (code "109") (name "unconnected-(J16-Pad4)") (class "Default")
      (node (ref "J16") (pin "4") (pinfunction "4_4") (pintype "passive+no_connect"))
    )
    (net (code "110") (name "unconnected-(J16-Pad5)") (class "Default")
      (node (ref "J16") (pin "5") (pinfunction "5_5") (pintype "passive+no_connect"))
    )
    (net (code "111") (name "unconnected-(J16-Pad6)") (class "Default")
      (node (ref "J16") (pin "6") (pinfunction "6_6") (pintype "passive+no_connect"))
    )
    (net (code "112") (name "unconnected-(J16-Pad7)") (class "Default")
      (node (ref "J16") (pin "7") (pinfunction "7_7") (pintype "passive"))
    )
    (net (code "113") (name "unconnected-(J16-Pad8)") (class "Default")
      (node (ref "J16") (pin "8") (pinfunction "8_8") (pintype "passive+no_connect"))
    )
    (net (code "114") (name "unconnected-(J16-Pad9)") (class "Default")
      (node (ref "J16") (pin "9") (pinfunction "9_9") (pintype "passive+no_connect"))
    )
    (net (code "115") (name "unconnected-(J16-SHIELD-PadSH1)") (class "Default")
      (node (ref "J16") (pin "SH1") (pinfunction "SHIELD_SH1") (pintype "passive+no_connect"))
    )
    (net (code "116") (name "unconnected-(J16-SHIELD-PadSH2)") (class "Default")
      (node (ref "J16") (pin "SH2") (pinfunction "SHIELD_SH2") (pintype "passive+no_connect"))
    )
    (net (code "117") (name "unconnected-(J17-Pad1)") (class "Default")
      (node (ref "J17") (pin "1") (pinfunction "1_1") (pintype "passive"))
    )
    (net (code "118") (name "unconnected-(J17-Pad3)") (class "Default")
      (node (ref "J17") (pin "3") (pinfunction "3_3") (pintype "passive"))
    )
    (net (code "119") (name "unconnected-(J17-Pad4)") (class "Default")
      (node (ref "J17") (pin "4") (pinfunction "4_4") (pintype "passive"))
    )
    (net (code "120") (name "unconnected-(J17-Pad5)") (class "Default")
      (node (ref "J17") (pin "5") (pinfunction "5_5") (pintype "passive"))
    )
    (net (code "121") (name "unconnected-(J18-Pad1)") (class "Default")
      (node (ref "J18") (pin "1") (pinfunction "1_1") (pintype "passive"))
    )
    (net (code "122") (name "unconnected-(J18-Pad3)") (class "Default")
      (node (ref "J18") (pin "3") (pinfunction "3_3") (pintype "passive"))
    )
    (net (code "123") (name "unconnected-(J18-Pad6)") (class "Default")
      (node (ref "J18") (pin "6") (pinfunction "6_6") (pintype "passive+no_connect"))
    )
    (net (code "124") (name "unconnected-(J19-Pad1)") (class "Default")
      (node (ref "J19") (pin "1") (pinfunction "1_1") (pintype "passive+no_connect"))
    )
    (net (code "125") (name "unconnected-(J19-Pad2)") (class "Default")
      (node (ref "J19") (pin "2") (pinfunction "2_2") (pintype "passive"))
    )
    (net (code "126") (name "unconnected-(J19-Pad4)") (class "Default")
      (node (ref "J19") (pin "4") (pinfunction "4_4") (pintype "passive+no_connect"))
    )
    (net (code "127") (name "unconnected-(J19-Pad5)") (class "Default")
      (node (ref "J19") (pin "5") (pinfunction "5_5") (pintype "passive+no_connect"))
    )
    (net (code "128") (name "unconnected-(J19-Pad6)") (class "Default")
      (node (ref "J19") (pin "6") (pinfunction "6_6") (pintype "passive+no_connect"))
    )
    (net (code "129") (name "unconnected-(J19-Pad7)") (class "Default")
      (node (ref "J19") (pin "7") (pinfunction "7_7") (pintype "passive"))
    )
    (net (code "130") (name "unconnected-(J19-Pad8)") (class "Default")
      (node (ref "J19") (pin "8") (pinfunction "8_8") (pintype "passive+no_connect"))
    )
    (net (code "131") (name "unconnected-(J19-Pad9)") (class "Default")
      (node (ref "J19") (pin "9") (pinfunction "9_9") (pintype "passive+no_connect"))
    )
    (net (code "132") (name "unconnected-(J19-SHIELD-PadSH1)") (class "Default")
      (node (ref "J19") (pin "SH1") (pinfunction "SHIELD_SH1") (pintype "passive+no_connect"))
    )
    (net (code "133") (name "unconnected-(J19-SHIELD-PadSH2)") (class "Default")
      (node (ref "J19") (pin "SH2") (pinfunction "SHIELD_SH2") (pintype "passive+no_connect"))
    )
    (net (code "134") (name "unconnected-(J20-Pad1)") (class "Default")
      (node (ref "J20") (pin "1") (pinfunction "1_1") (pintype "passive+no_connect"))
    )
    (net (code "135") (name "unconnected-(J20-Pad2)") (class "Default")
      (node (ref "J20") (pin "2") (pinfunction "2_2") (pintype "passive"))
    )
    (net (code "136") (name "unconnected-(J20-Pad3)") (class "Default")
      (node (ref "J20") (pin "3") (pinfunction "3_3") (pintype "passive"))
    )
    (net (code "137") (name "unconnected-(J20-Pad4)") (class "Default")
      (node (ref "J20") (pin "4") (pinfunction "4_4") (pintype "passive+no_connect"))
    )
    (net (code "138") (name "unconnected-(J20-Pad6)") (class "Default")
      (node (ref "J20") (pin "6") (pinfunction "6_6") (pintype "passive+no_connect"))
    )
    (net (code "139") (name "unconnected-(J20-Pad7)") (class "Default")
      (node (ref "J20") (pin "7") (pinfunction "7_7") (pintype "passive+no_connect"))
    )
    (net (code "140") (name "unconnected-(J20-Pad8)") (class "Default")
      (node (ref "J20") (pin "8") (pinfunction "8_8") (pintype "passive+no_connect"))
    )
    (net (code "141") (name "unconnected-(J20-Pad9)") (class "Default")
      (node (ref "J20") (pin "9") (pinfunction "9_9") (pintype "passive+no_connect"))
    )
    (net (code "142") (name "unconnected-(J20-SHIELD-PadSH1)") (class "Default")
      (node (ref "J20") (pin "SH1") (pinfunction "SHIELD_SH1") (pintype "passive+no_connect"))
    )
    (net (code "143") (name "unconnected-(J20-SHIELD-PadSH2)") (class "Default")
      (node (ref "J20") (pin "SH2") (pinfunction "SHIELD_SH2") (pintype "passive+no_connect"))
    )
    (net (code "144") (name "unconnected-(J21-Pad1)") (class "Default")
      (node (ref "J21") (pin "1") (pinfunction "1_1") (pintype "passive"))
    )
    (net (code "145") (name "unconnected-(J21-Pad3)") (class "Default")
      (node (ref "J21") (pin "3") (pinfunction "3_3") (pintype "passive"))
    )
    (net (code "146") (name "unconnected-(J21-Pad5)") (class "Default")
      (node (ref "J21") (pin "5") (pinfunction "5_5") (pintype "passive+no_connect"))
    )
    (net (code "147") (name "unconnected-(J22-Pad1)") (class "Default")
      (node (ref "J22") (pin "1") (pinfunction "1_1") (pintype "passive"))
    )
    (net (code "148") (name "unconnected-(J22-Pad3)") (class "Default")
      (node (ref "J22") (pin "3") (pinfunction "3_3") (pintype "passive"))
    )
    (net (code "149") (name "unconnected-(J22-Pad5)") (class "Default")
      (node (ref "J22") (pin "5") (pinfunction "5_5") (pintype "passive+no_connect"))
    )
    (net (code "150") (name "unconnected-(J23-Pad1)") (class "Default")
      (node (ref "J23") (pin "1") (pinfunction "1_1") (pintype "passive"))
    )
    (net (code "151") (name "unconnected-(J24-Pad1)") (class "Default")
      (node (ref "J24") (pin "1") (pinfunction "1_1") (pintype "passive"))
    )
    (net (code "152") (name "unconnected-(J25-Pad1)") (class "Default")
      (node (ref "J25") (pin "1") (pinfunction "1_1") (pintype "passive+no_connect"))
    )
    (net (code "153") (name "unconnected-(J25-Pad2)") (class "Default")
      (node (ref "J25") (pin "2") (pinfunction "2_2") (pintype "passive+no_connect"))
    )
    (net (code "154") (name "unconnected-(J25-Pad9)") (class "Default")
      (node (ref "J25") (pin "9") (pinfunction "9_9") (pintype "passive+no_connect"))
    )
    (net (code "155") (name "unconnected-(J25-Pad10)") (class "Default")
      (node (ref "J25") (pin "10") (pinfunction "10_10") (pintype "passive+no_connect"))
    )
    (net (code "156") (name "unconnected-(J26-Pad1)") (class "Default")
      (node (ref "J26") (pin "1") (pinfunction "1_1") (pintype "passive"))
    )
    (net (code "157") (name "unconnected-(J27-Pad1)") (class "Default")
      (node (ref "J27") (pin "1") (pinfunction "1_1") (pintype "passive"))
    )
  )
)
